# IvoOerlikon.net
KiCad netlist of a schematic drawn in EAGLE
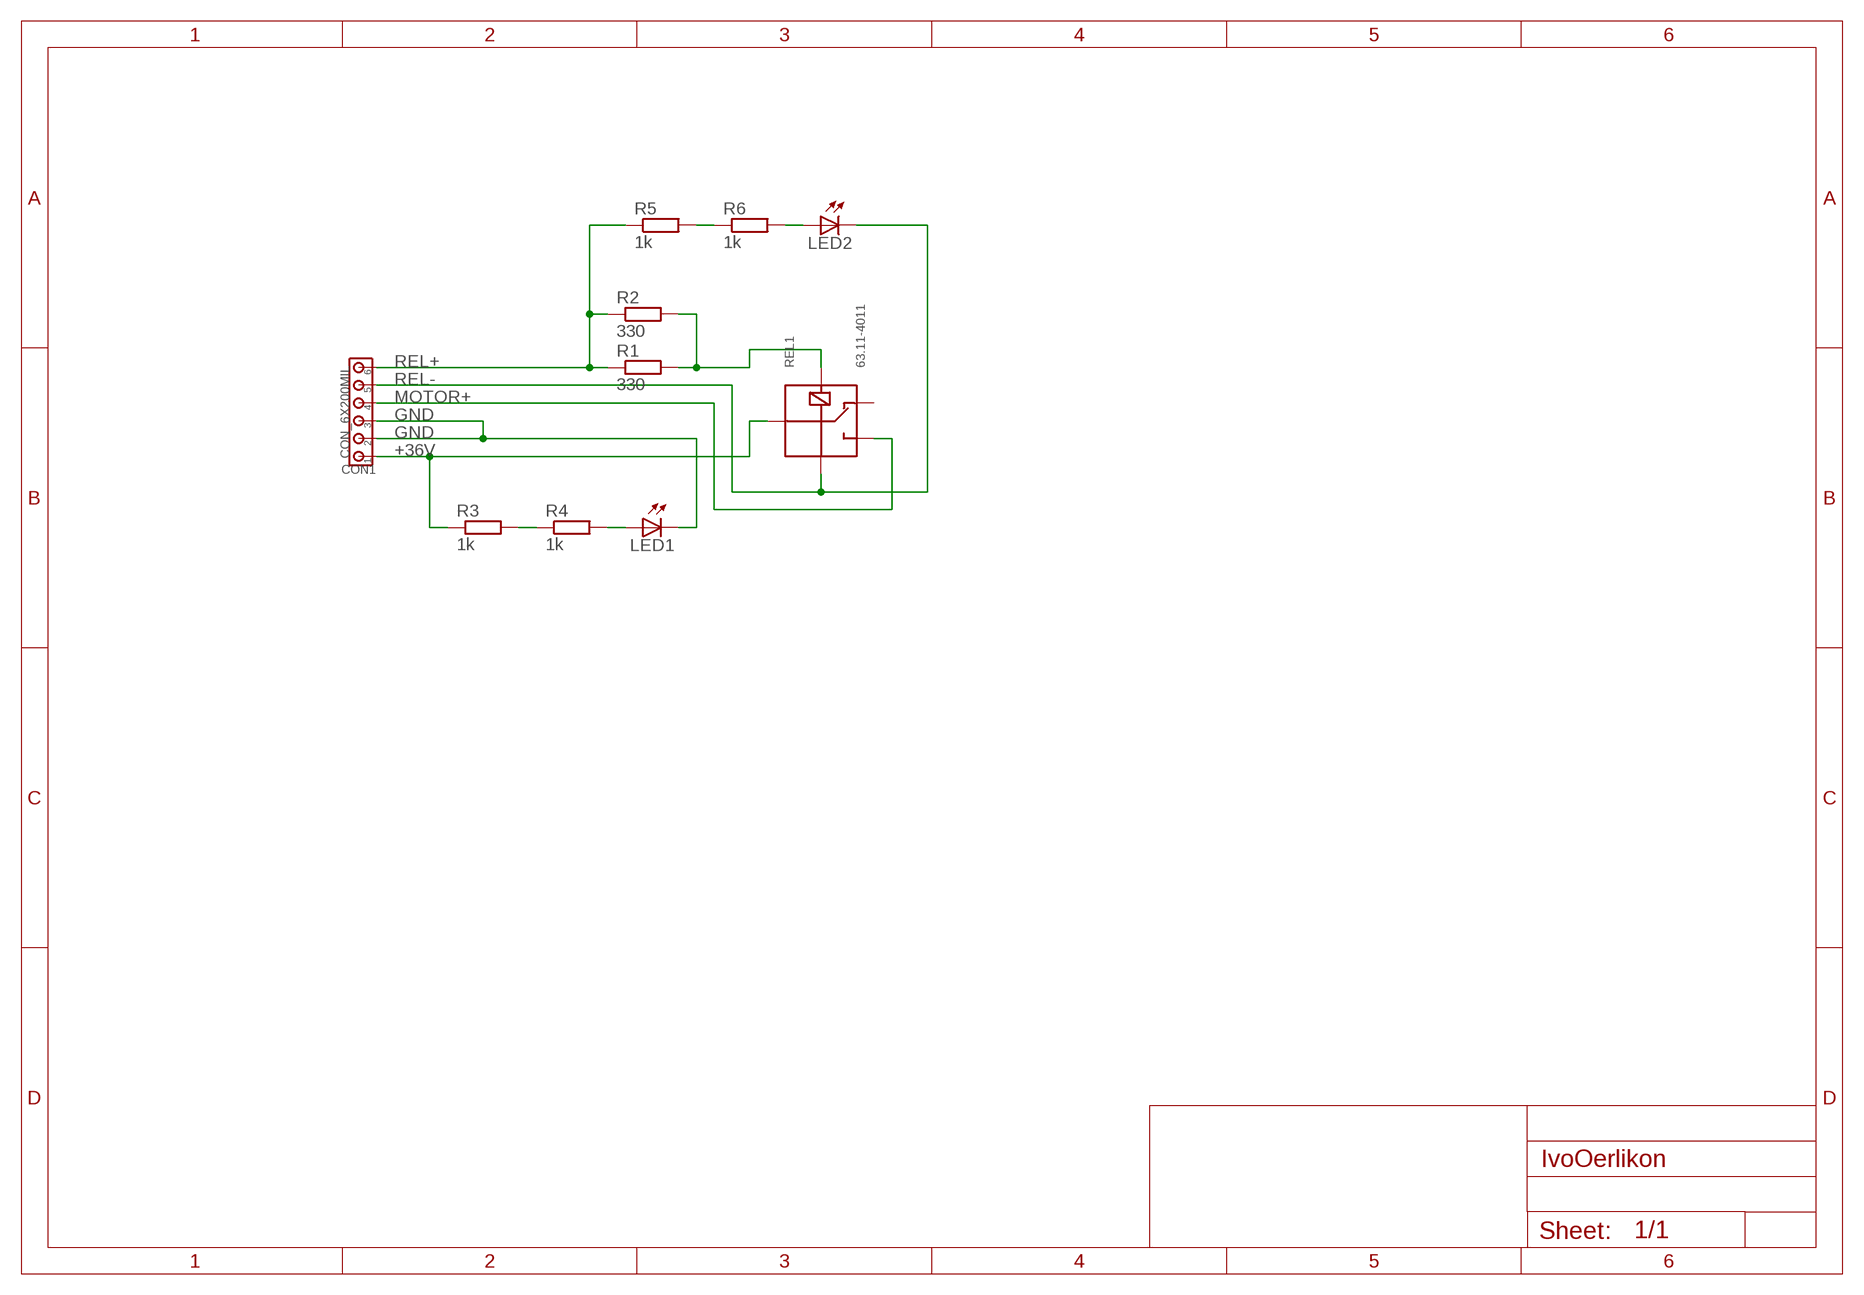
[diagram p0: schematic, sheet 1]

(export (version "E")
  (design (tool "Eeschema 10.0.6"))
  (components
    (comp (ref "CON1")
      (value "CON_6X200MIL")
      (footprint "eagle-import:200MIL_6X")
      (libsource (lib "eagle-import") (part "CON_6X200MIL"))
    )
    (comp (ref "LED1")
      (value "LED1206")
      (footprint "eagle-import:LED1206")
      (libsource (lib "eagle-import") (part "LED1206"))
    )
    (comp (ref "LED2")
      (value "LED1206")
      (footprint "eagle-import:LED1206")
      (libsource (lib "eagle-import") (part "LED1206"))
    )
    (comp (ref "R1")
      (value "330")
      (footprint "eagle-import:R1206")
      (libsource (lib "eagle-import") (part "RESISTORR1206"))
    )
    (comp (ref "R2")
      (value "330")
      (footprint "eagle-import:R1206")
      (libsource (lib "eagle-import") (part "RESISTORR1206"))
    )
    (comp (ref "R3")
      (value "1k")
      (footprint "eagle-import:R1206")
      (libsource (lib "eagle-import") (part "RESISTORR1206"))
    )
    (comp (ref "R4")
      (value "1k")
      (footprint "eagle-import:R1206")
      (libsource (lib "eagle-import") (part "RESISTORR1206"))
    )
    (comp (ref "R5")
      (value "1k")
      (footprint "eagle-import:R1206")
      (libsource (lib "eagle-import") (part "RESISTORR1206"))
    )
    (comp (ref "R6")
      (value "1k")
      (footprint "eagle-import:R1206")
      (libsource (lib "eagle-import") (part "RESISTORR1206"))
    )
    (comp (ref "REL1")
      (value "63.11-4011")
      (footprint "eagle-import:G5LE")
      (libsource (lib "eagle-import") (part "63.11-4011"))
    )
  )
  (nets
    (net (code "1") (name "/+36V") (class "Default")
      (node (ref "CON1") (pin "1") (pinfunction "1_1") (pintype "passive"))
      (node (ref "R3") (pin "1") (pinfunction "1_1") (pintype "passive"))
      (node (ref "REL1") (pin "COM") (pinfunction "COM_COM") (pintype "passive"))
    )
    (net (code "2") (name "/GND") (class "Default")
      (node (ref "CON1") (pin "2") (pinfunction "2_2") (pintype "passive"))
      (node (ref "CON1") (pin "3") (pinfunction "3_3") (pintype "passive"))
      (node (ref "LED1") (pin "C") (pinfunction "C_C") (pintype "passive"))
    )
    (net (code "3") (name "/MOTOR+") (class "Default")
      (node (ref "CON1") (pin "4") (pinfunction "4_4") (pintype "passive"))
      (node (ref "REL1") (pin "C") (pinfunction "C_C") (pintype "passive"))
    )
    (net (code "4") (name "/REL+") (class "Default")
      (node (ref "CON1") (pin "6") (pinfunction "6_6") (pintype "passive"))
      (node (ref "R1") (pin "1") (pinfunction "1_1") (pintype "passive"))
      (node (ref "R2") (pin "1") (pinfunction "1_1") (pintype "passive"))
      (node (ref "R5") (pin "1") (pinfunction "1_1") (pintype "passive"))
    )
    (net (code "5") (name "/REL-") (class "Default")
      (node (ref "CON1") (pin "5") (pinfunction "5_5") (pintype "passive"))
      (node (ref "LED2") (pin "C") (pinfunction "C_C") (pintype "passive"))
      (node (ref "REL1") (pin "1") (pinfunction "1_1") (pintype "passive"))
    )
    (net (code "6") (name "Net-(LED1-PadA)") (class "Default")
      (node (ref "LED1") (pin "A") (pinfunction "A_A") (pintype "passive"))
      (node (ref "R4") (pin "2") (pinfunction "2_2") (pintype "passive"))
    )
    (net (code "7") (name "Net-(LED2-PadA)") (class "Default")
      (node (ref "LED2") (pin "A") (pinfunction "A_A") (pintype "passive"))
      (node (ref "R6") (pin "2") (pinfunction "2_2") (pintype "passive"))
    )
    (net (code "8") (name "Net-(R1-Pad2)") (class "Default")
      (node (ref "R1") (pin "2") (pinfunction "2_2") (pintype "passive"))
      (node (ref "R2") (pin "2") (pinfunction "2_2") (pintype "passive"))
      (node (ref "REL1") (pin "2") (pinfunction "2_2") (pintype "passive"))
    )
    (net (code "9") (name "Net-(R3-Pad2)") (class "Default")
      (node (ref "R3") (pin "2") (pinfunction "2_2") (pintype "passive"))
      (node (ref "R4") (pin "1") (pinfunction "1_1") (pintype "passive"))
    )
    (net (code "10") (name "Net-(R5-Pad2)") (class "Default")
      (node (ref "R5") (pin "2") (pinfunction "2_2") (pintype "passive"))
      (node (ref "R6") (pin "1") (pinfunction "1_1") (pintype "passive"))
    )
    (net (code "11") (name "unconnected-(REL1-PadO)") (class "Default")
      (node (ref "REL1") (pin "O") (pinfunction "O_O") (pintype "passive"))
    )
  )
)
